# MV16_v1_4.net
KiCad netlist of a schematic drawn in EAGLE
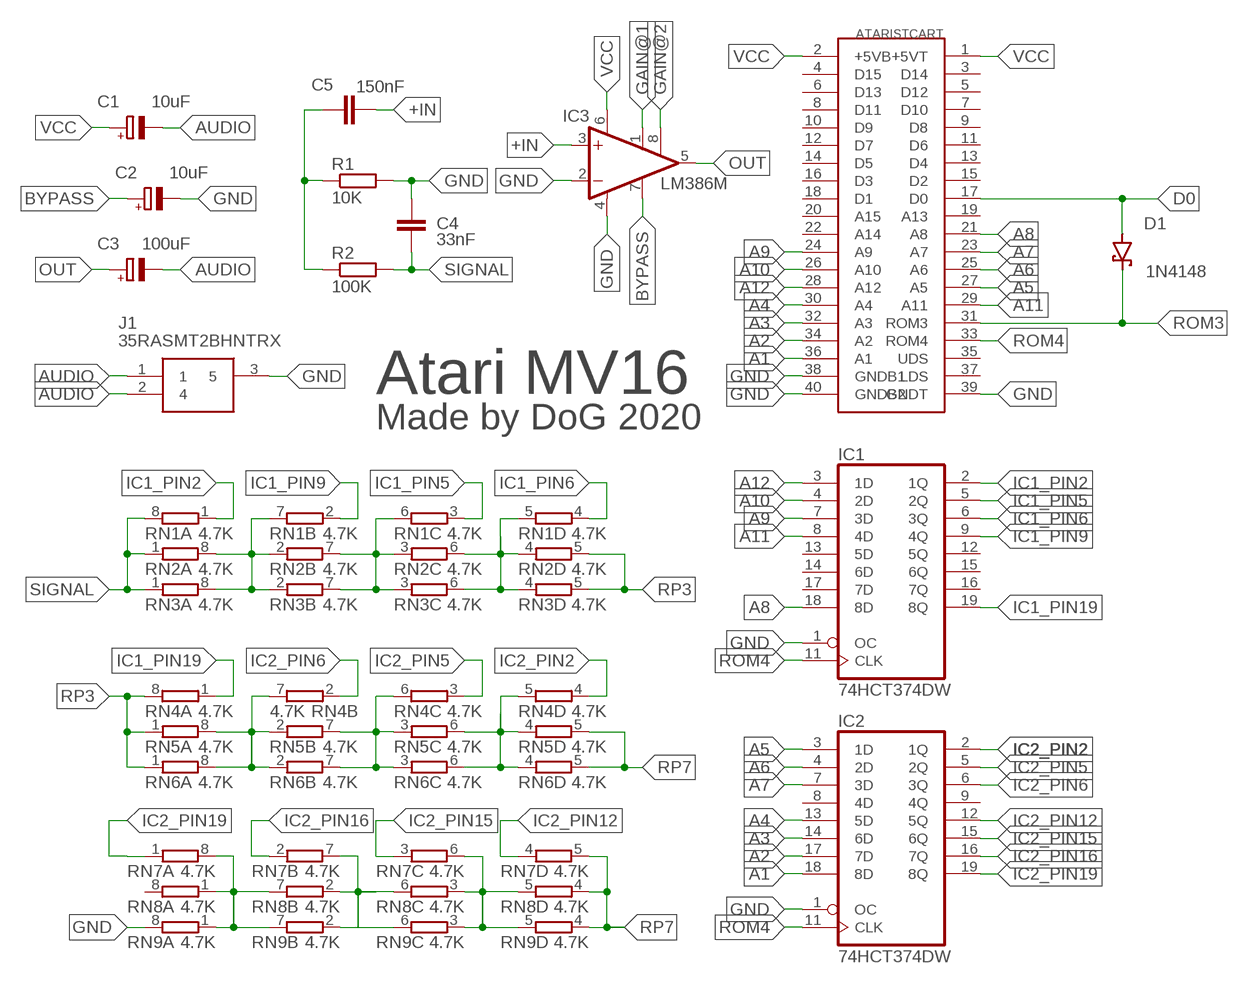
[diagram p0: schematic, sheet 1]

(export (version "E")
  (design (tool "Eeschema 10.0.6"))
  (components
    (comp (ref "C1")
      (value "10uF")
      (footprint "eagle-import:UD-5X5,8_NICHICON")
      (libsource (lib "eagle-import") (part "CPOL-EUUD-5X5,8"))
    )
    (comp (ref "C2")
      (value "10uF")
      (footprint "eagle-import:UD-5X5,8_NICHICON")
      (libsource (lib "eagle-import") (part "CPOL-EUUD-5X5,8"))
    )
    (comp (ref "C3")
      (value "100uF")
      (footprint "eagle-import:UD-6,3X7,7_NICHICON")
      (libsource (lib "eagle-import") (part "CPOL-EUUD-6,3X7,7"))
    )
    (comp (ref "C4")
      (value "33nF")
      (footprint "eagle-import:E_7260-38_NP")
      (libsource (lib "eagle-import") (part "C-EU"))
    )
    (comp (ref "C5")
      (value "150nF")
      (footprint "eagle-import:E_7260-38_NP")
      (libsource (lib "eagle-import") (part "C-EU"))
    )
    (comp (ref "D1")
      (value "1N4148")
      (footprint "eagle-import:SOD323_ST")
      (libsource (lib "eagle-import") (part "BAT60J"))
    )
    (comp (ref "IC1")
      (value "74HCT374DW")
      (footprint "eagle-import:SO20W")
      (libsource (lib "eagle-import") (part "74374DWHCT"))
    )
    (comp (ref "IC2")
      (value "74HCT374DW")
      (footprint "eagle-import:SO20W")
      (libsource (lib "eagle-import") (part "74374DWHCT"))
    )
    (comp (ref "IC3")
      (value "LM386M")
      (footprint "eagle-import:SO08")
      (libsource (lib "eagle-import") (part "LM386?-M1"))
    )
    (comp (ref "J1")
      (value "35RASMT2BHNTRX")
      (footprint "eagle-import:35RASMT2BHNTRX_1")
      (fields (field (name "MOUSER_PART_NUMBER") "502-35RASMT2BHNTRX"))
      (libsource (lib "eagle-import") (part "35RASMT2BHNTRX"))
    )
    (comp (ref "P1")
      (value "ATARI_ST_CART_FIXED")
      (footprint "eagle-import:ATARI_ST_CART")
      (libsource (lib "eagle-import") (part "ATARI_ST_CART_FIXED"))
    )
    (comp (ref "R1")
      (value "10K")
      (footprint "eagle-import:R0805")
      (libsource (lib "eagle-import") (part "R-EU_R0805"))
    )
    (comp (ref "R2")
      (value "100K")
      (footprint "eagle-import:R0805")
      (libsource (lib "eagle-import") (part "R-EU_R0805"))
    )
    (comp (ref "RN1")
      (value "4.7K")
      (footprint "eagle-import:EXBV8V")
      (libsource (lib "eagle-import") (part "4R-NEXBV8V"))
    )
    (comp (ref "RN2")
      (value "4.7K")
      (footprint "eagle-import:EXBV8V")
      (libsource (lib "eagle-import") (part "4R-NEXBV8V"))
    )
    (comp (ref "RN3")
      (value "4.7K")
      (footprint "eagle-import:EXBV8V")
      (libsource (lib "eagle-import") (part "4R-NEXBV8V"))
    )
    (comp (ref "RN4")
      (value "4.7K")
      (footprint "eagle-import:EXBV8V")
      (libsource (lib "eagle-import") (part "4R-NEXBV8V"))
    )
    (comp (ref "RN5")
      (value "4.7K")
      (footprint "eagle-import:EXBV8V")
      (libsource (lib "eagle-import") (part "4R-NEXBV8V"))
    )
    (comp (ref "RN6")
      (value "4.7K")
      (footprint "eagle-import:EXBV8V")
      (libsource (lib "eagle-import") (part "4R-NEXBV8V"))
    )
    (comp (ref "RN7")
      (value "4.7K")
      (footprint "eagle-import:EXBV8V")
      (libsource (lib "eagle-import") (part "4R-NEXBV8V"))
    )
    (comp (ref "RN8")
      (value "4.7K")
      (footprint "eagle-import:EXBV8V")
      (libsource (lib "eagle-import") (part "4R-NEXBV8V"))
    )
    (comp (ref "RN9")
      (value "4.7K")
      (footprint "eagle-import:EXBV8V")
      (libsource (lib "eagle-import") (part "4R-NEXBV8V"))
    )
  )
  (nets
    (net (code "1") (name "+IN") (class "Default")
      (node (ref "C5") (pin "-") (pinfunction "2_-") (pintype "passive"))
      (node (ref "IC3") (pin "3") (pinfunction "+IN_3") (pintype "input"))
    )
    (net (code "2") (name "A1") (class "Default")
      (node (ref "IC2") (pin "18") (pinfunction "8D_18") (pintype "input"))
      (node (ref "P1") (pin "36") (pinfunction "A1_36") (pintype "output"))
    )
    (net (code "3") (name "A2") (class "Default")
      (node (ref "IC2") (pin "17") (pinfunction "7D_17") (pintype "input"))
      (node (ref "P1") (pin "34") (pinfunction "A2_34") (pintype "output"))
    )
    (net (code "4") (name "A3") (class "Default")
      (node (ref "IC2") (pin "14") (pinfunction "6D_14") (pintype "input"))
      (node (ref "P1") (pin "32") (pinfunction "A3_32") (pintype "output"))
    )
    (net (code "5") (name "A4") (class "Default")
      (node (ref "IC2") (pin "13") (pinfunction "5D_13") (pintype "input"))
      (node (ref "P1") (pin "30") (pinfunction "A4_30") (pintype "output"))
    )
    (net (code "6") (name "A5") (class "Default")
      (node (ref "IC2") (pin "3") (pinfunction "1D_3") (pintype "input"))
      (node (ref "P1") (pin "27") (pinfunction "A5_27") (pintype "output"))
    )
    (net (code "7") (name "A6") (class "Default")
      (node (ref "IC2") (pin "4") (pinfunction "2D_4") (pintype "input"))
      (node (ref "P1") (pin "25") (pinfunction "A6_25") (pintype "output"))
    )
    (net (code "8") (name "A7") (class "Default")
      (node (ref "IC2") (pin "7") (pinfunction "3D_7") (pintype "input"))
      (node (ref "P1") (pin "23") (pinfunction "A7_23") (pintype "output"))
    )
    (net (code "9") (name "A8") (class "Default")
      (node (ref "IC1") (pin "18") (pinfunction "8D_18") (pintype "input"))
      (node (ref "P1") (pin "21") (pinfunction "A8_21") (pintype "output"))
    )
    (net (code "10") (name "A9") (class "Default")
      (node (ref "IC1") (pin "7") (pinfunction "3D_7") (pintype "input"))
      (node (ref "P1") (pin "24") (pinfunction "A9_24") (pintype "output"))
    )
    (net (code "11") (name "A10") (class "Default")
      (node (ref "IC1") (pin "4") (pinfunction "2D_4") (pintype "input"))
      (node (ref "P1") (pin "26") (pinfunction "A10_26") (pintype "output"))
    )
    (net (code "12") (name "A11") (class "Default")
      (node (ref "IC1") (pin "8") (pinfunction "4D_8") (pintype "input"))
      (node (ref "P1") (pin "29") (pinfunction "A11_29") (pintype "output"))
    )
    (net (code "13") (name "A12") (class "Default")
      (node (ref "IC1") (pin "3") (pinfunction "1D_3") (pintype "input"))
      (node (ref "P1") (pin "28") (pinfunction "A12_28") (pintype "output"))
    )
    (net (code "14") (name "AUDIO") (class "Default")
      (node (ref "C1") (pin "-") (pinfunction "-_-") (pintype "passive"))
      (node (ref "C3") (pin "-") (pinfunction "-_-") (pintype "passive"))
      (node (ref "J1") (pin "1") (pinfunction "1_1") (pintype "bidirectional"))
      (node (ref "J1") (pin "2") (pinfunction "4_2") (pintype "bidirectional"))
    )
    (net (code "15") (name "BYPASS") (class "Default")
      (node (ref "C2") (pin "+") (pinfunction "+_+") (pintype "passive"))
      (node (ref "IC3") (pin "7") (pinfunction "BYPASS_7") (pintype "passive"))
    )
    (net (code "16") (name "D0") (class "Default")
      (node (ref "D1") (pin "A") (pinfunction "A_A") (pintype "passive"))
      (node (ref "P1") (pin "17") (pinfunction "D0_17") (pintype "input"))
    )
    (net (code "17") (name "GAIN@1") (class "Default")
      (node (ref "IC3") (pin "1") (pinfunction "GAIN_1") (pintype "passive"))
    )
    (net (code "18") (name "GAIN@2") (class "Default")
      (node (ref "IC3") (pin "8") (pinfunction "GAIN_8") (pintype "passive"))
    )
    (net (code "19") (name "GND") (class "Default")
      (node (ref "C2") (pin "-") (pinfunction "-_-") (pintype "passive"))
      (node (ref "C4") (pin "-") (pinfunction "2_-") (pintype "passive"))
      (node (ref "IC1") (pin "1") (pinfunction "OC_1") (pintype "input"))
      (node (ref "IC2") (pin "1") (pinfunction "OC_1") (pintype "input"))
      (node (ref "IC3") (pin "2") (pinfunction "-IN_2") (pintype "input"))
      (node (ref "IC3") (pin "4") (pinfunction "GND_4") (pintype "power_in"))
      (node (ref "J1") (pin "3") (pinfunction "5_3") (pintype "bidirectional"))
      (node (ref "P1") (pin "38") (pinfunction "GNDB1_38") (pintype "power_in"))
      (node (ref "P1") (pin "39") (pinfunction "GNDT_39") (pintype "power_in"))
      (node (ref "P1") (pin "40") (pinfunction "GNDB2_40") (pintype "power_in"))
      (node (ref "R1") (pin "2") (pinfunction "2_2") (pintype "passive"))
      (node (ref "RN9") (pin "8") (pinfunction "2_8") (pintype "passive"))
    )
    (net (code "20") (name "IC1_PIN2") (class "Default")
      (node (ref "IC1") (pin "2") (pinfunction "1Q_2") (pintype "tri_state"))
      (node (ref "RN1") (pin "1") (pinfunction "1_1") (pintype "passive"))
    )
    (net (code "21") (name "IC1_PIN5") (class "Default")
      (node (ref "IC1") (pin "5") (pinfunction "2Q_5") (pintype "tri_state"))
      (node (ref "RN1") (pin "3") (pinfunction "1_3") (pintype "passive"))
    )
    (net (code "22") (name "IC1_PIN6") (class "Default")
      (node (ref "IC1") (pin "6") (pinfunction "3Q_6") (pintype "tri_state"))
      (node (ref "RN1") (pin "4") (pinfunction "1_4") (pintype "passive"))
    )
    (net (code "23") (name "IC1_PIN9") (class "Default")
      (node (ref "IC1") (pin "9") (pinfunction "4Q_9") (pintype "tri_state"))
      (node (ref "RN1") (pin "2") (pinfunction "1_2") (pintype "passive"))
    )
    (net (code "24") (name "IC1_PIN19") (class "Default")
      (node (ref "IC1") (pin "19") (pinfunction "8Q_19") (pintype "tri_state"))
      (node (ref "RN4") (pin "1") (pinfunction "1_1") (pintype "passive"))
    )
    (net (code "25") (name "IC2_PIN2") (class "Default")
      (node (ref "IC2") (pin "2") (pinfunction "1Q_2") (pintype "tri_state"))
      (node (ref "RN4") (pin "4") (pinfunction "1_4") (pintype "passive"))
    )
    (net (code "26") (name "IC2_PIN5") (class "Default")
      (node (ref "IC2") (pin "5") (pinfunction "2Q_5") (pintype "tri_state"))
      (node (ref "RN4") (pin "3") (pinfunction "1_3") (pintype "passive"))
    )
    (net (code "27") (name "IC2_PIN6") (class "Default")
      (node (ref "IC2") (pin "6") (pinfunction "3Q_6") (pintype "tri_state"))
      (node (ref "RN4") (pin "2") (pinfunction "1_2") (pintype "passive"))
    )
    (net (code "28") (name "IC2_PIN12") (class "Default")
      (node (ref "IC2") (pin "12") (pinfunction "5Q_12") (pintype "tri_state"))
      (node (ref "RN7") (pin "4") (pinfunction "1_4") (pintype "passive"))
    )
    (net (code "29") (name "IC2_PIN15") (class "Default")
      (node (ref "IC2") (pin "15") (pinfunction "6Q_15") (pintype "tri_state"))
      (node (ref "RN7") (pin "3") (pinfunction "1_3") (pintype "passive"))
    )
    (net (code "30") (name "IC2_PIN16") (class "Default")
      (node (ref "IC2") (pin "16") (pinfunction "7Q_16") (pintype "tri_state"))
      (node (ref "RN7") (pin "2") (pinfunction "1_2") (pintype "passive"))
    )
    (net (code "31") (name "IC2_PIN19") (class "Default")
      (node (ref "IC2") (pin "19") (pinfunction "8Q_19") (pintype "tri_state"))
      (node (ref "RN7") (pin "1") (pinfunction "1_1") (pintype "passive"))
    )
    (net (code "32") (name "Net-(C5-1)") (class "Default")
      (node (ref "C5") (pin "+") (pinfunction "1_+") (pintype "passive"))
      (node (ref "R1") (pin "1") (pinfunction "1_1") (pintype "passive"))
      (node (ref "R2") (pin "1") (pinfunction "1_1") (pintype "passive"))
    )
    (net (code "33") (name "Net-(RN1B-2)") (class "Default")
      (node (ref "RN1") (pin "7") (pinfunction "2_7") (pintype "passive"))
      (node (ref "RN2") (pin "2") (pinfunction "1_2") (pintype "passive"))
      (node (ref "RN2") (pin "8") (pinfunction "2_8") (pintype "passive"))
      (node (ref "RN3") (pin "2") (pinfunction "1_2") (pintype "passive"))
      (node (ref "RN3") (pin "8") (pinfunction "2_8") (pintype "passive"))
    )
    (net (code "34") (name "Net-(RN1C-2)") (class "Default")
      (node (ref "RN1") (pin "6") (pinfunction "2_6") (pintype "passive"))
      (node (ref "RN2") (pin "3") (pinfunction "1_3") (pintype "passive"))
      (node (ref "RN2") (pin "7") (pinfunction "2_7") (pintype "passive"))
      (node (ref "RN3") (pin "3") (pinfunction "1_3") (pintype "passive"))
      (node (ref "RN3") (pin "7") (pinfunction "2_7") (pintype "passive"))
    )
    (net (code "35") (name "Net-(RN1D-2)") (class "Default")
      (node (ref "RN1") (pin "5") (pinfunction "2_5") (pintype "passive"))
      (node (ref "RN2") (pin "4") (pinfunction "1_4") (pintype "passive"))
      (node (ref "RN2") (pin "6") (pinfunction "2_6") (pintype "passive"))
      (node (ref "RN3") (pin "4") (pinfunction "1_4") (pintype "passive"))
      (node (ref "RN3") (pin "6") (pinfunction "2_6") (pintype "passive"))
    )
    (net (code "36") (name "Net-(RN4B-2)") (class "Default")
      (node (ref "RN4") (pin "7") (pinfunction "2_7") (pintype "passive"))
      (node (ref "RN5") (pin "2") (pinfunction "1_2") (pintype "passive"))
      (node (ref "RN5") (pin "8") (pinfunction "2_8") (pintype "passive"))
      (node (ref "RN6") (pin "2") (pinfunction "1_2") (pintype "passive"))
      (node (ref "RN6") (pin "8") (pinfunction "2_8") (pintype "passive"))
    )
    (net (code "37") (name "Net-(RN4C-2)") (class "Default")
      (node (ref "RN4") (pin "6") (pinfunction "2_6") (pintype "passive"))
      (node (ref "RN5") (pin "3") (pinfunction "1_3") (pintype "passive"))
      (node (ref "RN5") (pin "7") (pinfunction "2_7") (pintype "passive"))
      (node (ref "RN6") (pin "3") (pinfunction "1_3") (pintype "passive"))
      (node (ref "RN6") (pin "7") (pinfunction "2_7") (pintype "passive"))
    )
    (net (code "38") (name "Net-(RN4D-2)") (class "Default")
      (node (ref "RN4") (pin "5") (pinfunction "2_5") (pintype "passive"))
      (node (ref "RN5") (pin "4") (pinfunction "1_4") (pintype "passive"))
      (node (ref "RN5") (pin "6") (pinfunction "2_6") (pintype "passive"))
      (node (ref "RN6") (pin "4") (pinfunction "1_4") (pintype "passive"))
      (node (ref "RN6") (pin "6") (pinfunction "2_6") (pintype "passive"))
    )
    (net (code "39") (name "Net-(RN7A-2)") (class "Default")
      (node (ref "RN7") (pin "8") (pinfunction "2_8") (pintype "passive"))
      (node (ref "RN8") (pin "1") (pinfunction "1_1") (pintype "passive"))
      (node (ref "RN8") (pin "7") (pinfunction "2_7") (pintype "passive"))
      (node (ref "RN9") (pin "1") (pinfunction "1_1") (pintype "passive"))
      (node (ref "RN9") (pin "7") (pinfunction "2_7") (pintype "passive"))
    )
    (net (code "40") (name "Net-(RN7B-2)") (class "Default")
      (node (ref "RN7") (pin "7") (pinfunction "2_7") (pintype "passive"))
      (node (ref "RN8") (pin "2") (pinfunction "1_2") (pintype "passive"))
      (node (ref "RN8") (pin "6") (pinfunction "2_6") (pintype "passive"))
      (node (ref "RN9") (pin "2") (pinfunction "1_2") (pintype "passive"))
      (node (ref "RN9") (pin "6") (pinfunction "2_6") (pintype "passive"))
    )
    (net (code "41") (name "Net-(RN7C-2)") (class "Default")
      (node (ref "RN7") (pin "6") (pinfunction "2_6") (pintype "passive"))
      (node (ref "RN8") (pin "3") (pinfunction "1_3") (pintype "passive"))
      (node (ref "RN8") (pin "5") (pinfunction "2_5") (pintype "passive"))
      (node (ref "RN9") (pin "3") (pinfunction "1_3") (pintype "passive"))
      (node (ref "RN9") (pin "5") (pinfunction "2_5") (pintype "passive"))
    )
    (net (code "42") (name "OUT") (class "Default")
      (node (ref "C3") (pin "+") (pinfunction "+_+") (pintype "passive"))
      (node (ref "IC3") (pin "5") (pinfunction "OUT_5") (pintype "output"))
    )
    (net (code "43") (name "ROM3") (class "Default")
      (node (ref "D1") (pin "C") (pinfunction "C_C") (pintype "passive"))
      (node (ref "P1") (pin "31") (pinfunction "ROM3_31") (pintype "output"))
    )
    (net (code "44") (name "ROM4") (class "Default")
      (node (ref "IC1") (pin "11") (pinfunction "CLK_11") (pintype "input"))
      (node (ref "IC2") (pin "11") (pinfunction "CLK_11") (pintype "input"))
      (node (ref "P1") (pin "33") (pinfunction "ROM4_33") (pintype "output"))
    )
    (net (code "45") (name "RP3") (class "Default")
      (node (ref "RN2") (pin "5") (pinfunction "2_5") (pintype "passive"))
      (node (ref "RN3") (pin "5") (pinfunction "2_5") (pintype "passive"))
      (node (ref "RN4") (pin "8") (pinfunction "2_8") (pintype "passive"))
      (node (ref "RN5") (pin "1") (pinfunction "1_1") (pintype "passive"))
      (node (ref "RN6") (pin "1") (pinfunction "1_1") (pintype "passive"))
    )
    (net (code "46") (name "RP7") (class "Default")
      (node (ref "RN5") (pin "5") (pinfunction "2_5") (pintype "passive"))
      (node (ref "RN6") (pin "5") (pinfunction "2_5") (pintype "passive"))
      (node (ref "RN7") (pin "5") (pinfunction "2_5") (pintype "passive"))
      (node (ref "RN8") (pin "4") (pinfunction "1_4") (pintype "passive"))
      (node (ref "RN9") (pin "4") (pinfunction "1_4") (pintype "passive"))
    )
    (net (code "47") (name "SIGNAL") (class "Default")
      (node (ref "C4") (pin "+") (pinfunction "1_+") (pintype "passive"))
      (node (ref "R2") (pin "2") (pinfunction "2_2") (pintype "passive"))
      (node (ref "RN1") (pin "8") (pinfunction "2_8") (pintype "passive"))
      (node (ref "RN2") (pin "1") (pinfunction "1_1") (pintype "passive"))
      (node (ref "RN3") (pin "1") (pinfunction "1_1") (pintype "passive"))
    )
    (net (code "48") (name "VCC") (class "Default")
      (node (ref "C1") (pin "+") (pinfunction "+_+") (pintype "passive"))
      (node (ref "IC3") (pin "6") (pinfunction "VS_6") (pintype "power_in"))
      (node (ref "P1") (pin "1") (pinfunction "+5VT_1") (pintype "power_in"))
      (node (ref "P1") (pin "2") (pinfunction "+5VB_2") (pintype "power_in"))
    )
    (net (code "49") (name "unconnected-(IC1A-5D-Pad13)") (class "Default")
      (node (ref "IC1") (pin "13") (pinfunction "5D_13") (pintype "input"))
    )
    (net (code "50") (name "unconnected-(IC1A-5Q-Pad12)") (class "Default")
      (node (ref "IC1") (pin "12") (pinfunction "5Q_12") (pintype "tri_state"))
    )
    (net (code "51") (name "unconnected-(IC1A-6D-Pad14)") (class "Default")
      (node (ref "IC1") (pin "14") (pinfunction "6D_14") (pintype "input"))
    )
    (net (code "52") (name "unconnected-(IC1A-6Q-Pad15)") (class "Default")
      (node (ref "IC1") (pin "15") (pinfunction "6Q_15") (pintype "tri_state"))
    )
    (net (code "53") (name "unconnected-(IC1A-7D-Pad17)") (class "Default")
      (node (ref "IC1") (pin "17") (pinfunction "7D_17") (pintype "input"))
    )
    (net (code "54") (name "unconnected-(IC1A-7Q-Pad16)") (class "Default")
      (node (ref "IC1") (pin "16") (pinfunction "7Q_16") (pintype "tri_state"))
    )
    (net (code "55") (name "unconnected-(IC2A-4D-Pad8)") (class "Default")
      (node (ref "IC2") (pin "8") (pinfunction "4D_8") (pintype "input"))
    )
    (net (code "56") (name "unconnected-(IC2A-4Q-Pad9)") (class "Default")
      (node (ref "IC2") (pin "9") (pinfunction "4Q_9") (pintype "tri_state"))
    )
    (net (code "57") (name "unconnected-(P1-A13-Pad19)") (class "Default")
      (node (ref "P1") (pin "19") (pinfunction "A13_19") (pintype "output"))
    )
    (net (code "58") (name "unconnected-(P1-A14-Pad22)") (class "Default")
      (node (ref "P1") (pin "22") (pinfunction "A14_22") (pintype "output"))
    )
    (net (code "59") (name "unconnected-(P1-A15-Pad20)") (class "Default")
      (node (ref "P1") (pin "20") (pinfunction "A15_20") (pintype "output"))
    )
    (net (code "60") (name "unconnected-(P1-D1-Pad18)") (class "Default")
      (node (ref "P1") (pin "18") (pinfunction "D1_18") (pintype "input"))
    )
    (net (code "61") (name "unconnected-(P1-D2-Pad15)") (class "Default")
      (node (ref "P1") (pin "15") (pinfunction "D2_15") (pintype "input"))
    )
    (net (code "62") (name "unconnected-(P1-D3-Pad16)") (class "Default")
      (node (ref "P1") (pin "16") (pinfunction "D3_16") (pintype "input"))
    )
    (net (code "63") (name "unconnected-(P1-D4-Pad13)") (class "Default")
      (node (ref "P1") (pin "13") (pinfunction "D4_13") (pintype "input"))
    )
    (net (code "64") (name "unconnected-(P1-D5-Pad14)") (class "Default")
      (node (ref "P1") (pin "14") (pinfunction "D5_14") (pintype "input"))
    )
    (net (code "65") (name "unconnected-(P1-D6-Pad11)") (class "Default")
      (node (ref "P1") (pin "11") (pinfunction "D6_11") (pintype "input"))
    )
    (net (code "66") (name "unconnected-(P1-D7-Pad12)") (class "Default")
      (node (ref "P1") (pin "12") (pinfunction "D7_12") (pintype "input"))
    )
    (net (code "67") (name "unconnected-(P1-D8-Pad9)") (class "Default")
      (node (ref "P1") (pin "9") (pinfunction "D8_9") (pintype "input"))
    )
    (net (code "68") (name "unconnected-(P1-D9-Pad10)") (class "Default")
      (node (ref "P1") (pin "10") (pinfunction "D9_10") (pintype "input"))
    )
    (net (code "69") (name "unconnected-(P1-D10-Pad7)") (class "Default")
      (node (ref "P1") (pin "7") (pinfunction "D10_7") (pintype "input"))
    )
    (net (code "70") (name "unconnected-(P1-D11-Pad8)") (class "Default")
      (node (ref "P1") (pin "8") (pinfunction "D11_8") (pintype "input"))
    )
    (net (code "71") (name "unconnected-(P1-D12-Pad5)") (class "Default")
      (node (ref "P1") (pin "5") (pinfunction "D12_5") (pintype "input"))
    )
    (net (code "72") (name "unconnected-(P1-D13-Pad6)") (class "Default")
      (node (ref "P1") (pin "6") (pinfunction "D13_6") (pintype "input"))
    )
    (net (code "73") (name "unconnected-(P1-D14-Pad3)") (class "Default")
      (node (ref "P1") (pin "3") (pinfunction "D14_3") (pintype "input"))
    )
    (net (code "74") (name "unconnected-(P1-D15-Pad4)") (class "Default")
      (node (ref "P1") (pin "4") (pinfunction "D15_4") (pintype "input"))
    )
    (net (code "75") (name "unconnected-(P1-LDS-Pad37)") (class "Default")
      (node (ref "P1") (pin "37") (pinfunction "LDS_37") (pintype "output"))
    )
    (net (code "76") (name "unconnected-(P1-UDS-Pad35)") (class "Default")
      (node (ref "P1") (pin "35") (pinfunction "UDS_35") (pintype "output"))
    )
    (net (code "77") (name "unconnected-(RN8A-2-Pad8)") (class "Default")
      (node (ref "RN8") (pin "8") (pinfunction "2_8") (pintype "passive"))
    )
  )
)
